# schematic_slave2_rotary.net
KiCad netlist of a schematic drawn in EAGLE
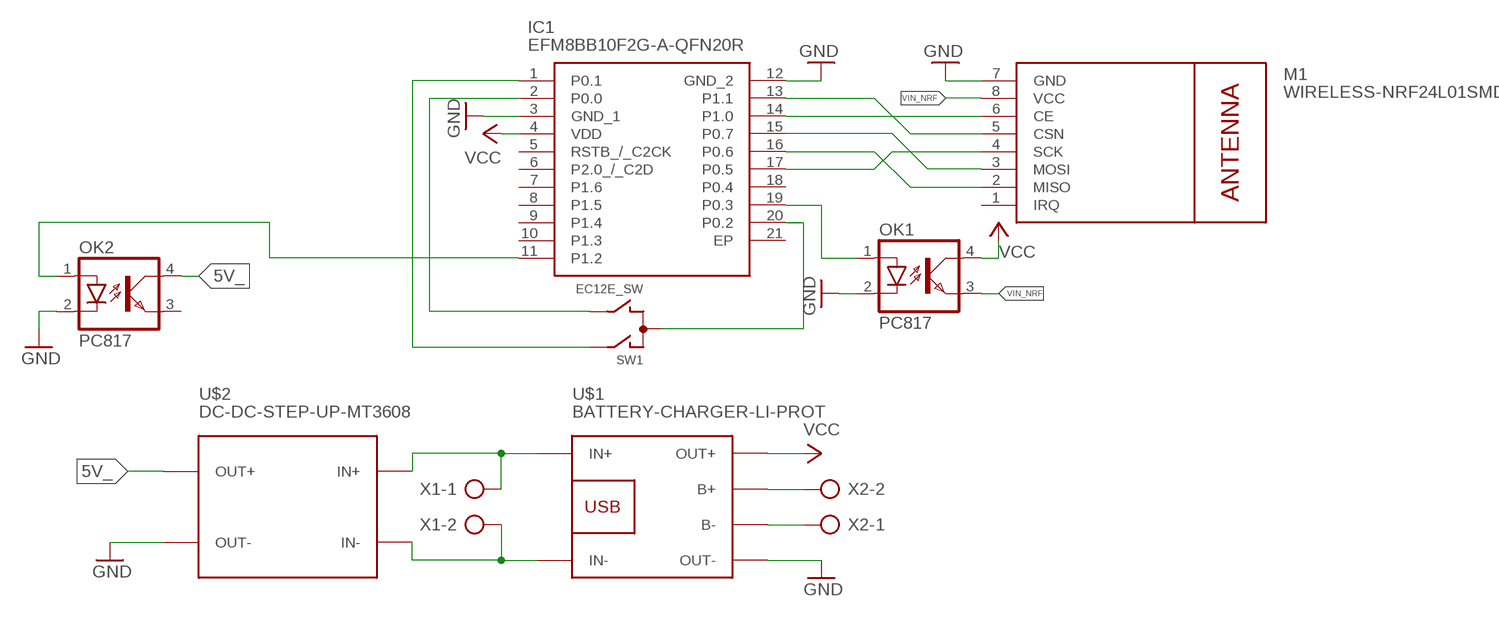
[diagram p0: schematic, sheet 1]

(export (version "E")
  (design (tool "Eeschema 10.0.6"))
  (components
    (comp (ref "IC1")
      (value "EFM8BB10F2G-A-QFN20R")
      (footprint "eagle-import:EFM8BB10F2GAQFN20R")
      (fields (field (name "MOUSER_PART_NUMBER") "634-8BB10F2GAQF20R"))
      (libsource (lib "eagle-import") (part "EFM8BB10F2G-A-QFN20R"))
    )
    (comp (ref "M1")
      (value "WIRELESS-NRF24L01SMD")
      (footprint "eagle-import:WIRELESS-NRF24L01-SMD")
      (libsource (lib "eagle-import") (part "WIRELESS-NRF24L01SMD"))
    )
    (comp (ref "OK1")
      (value "PC817")
      (footprint "eagle-import:DIL04")
      (fields (field (name "MPN") "PC817X4J000F"))
      (libsource (lib "eagle-import") (part "PC817"))
    )
    (comp (ref "OK2")
      (value "PC817")
      (footprint "eagle-import:DIL04")
      (fields (field (name "MPN") "PC817X4J000F"))
      (libsource (lib "eagle-import") (part "PC817"))
    )
    (comp (ref "SW1")
      (value "EC12E_SW")
      (footprint "eagle-import:ALPS_EC12E_SW")
      (fields (field (name "MPN") "EC12E2424407"))
      (libsource (lib "eagle-import") (part "EC12E_SW"))
    )
    (comp (ref "U$1")
      (value "BATTERY-CHARGER-LI-PROT")
      (footprint "eagle-import:BATTERY-CHARGER-LI-PROT")
      (libsource (lib "eagle-import") (part "BATTERY-CHARGER-LI-PROT"))
    )
    (comp (ref "U$2")
      (value "DC-DC-STEP-UP-MT3608")
      (footprint "eagle-import:DC-DC-STEP-UP-MT3608")
      (libsource (lib "eagle-import") (part "DC-DC-STEP-UP-MT3608"))
    )
    (comp (ref "X1")
      (value "AK500/2-H")
      (footprint "eagle-import:AK500_2-H")
      (libsource (lib "eagle-import") (part "AK500/2-H"))
    )
    (comp (ref "X2")
      (value "AK500/2-H")
      (footprint "eagle-import:AK500_2-H")
      (libsource (lib "eagle-import") (part "AK500/2-H"))
    )
  )
  (nets
    (net (code "1") (name "5V_") (class "Default")
      (node (ref "OK2") (pin "4") (pinfunction "COL_4") (pintype "passive"))
      (node (ref "U$2") (pin "OUT+") (pinfunction "OUT+_OUT+") (pintype "bidirectional"))
    )
    (net (code "2") (name "GND") (class "Default")
      (node (ref "IC1") (pin "12") (pinfunction "GND_2_12") (pintype "bidirectional"))
      (node (ref "IC1") (pin "3") (pinfunction "GND_1_3") (pintype "bidirectional"))
      (node (ref "M1") (pin "7") (pinfunction "GND_7") (pintype "power_in"))
      (node (ref "OK1") (pin "2") (pinfunction "C_2") (pintype "passive"))
      (node (ref "OK2") (pin "2") (pinfunction "C_2") (pintype "passive"))
      (node (ref "U$1") (pin "OUT-") (pinfunction "OUT-_OUT-") (pintype "bidirectional"))
      (node (ref "U$2") (pin "OUT-") (pinfunction "OUT-_OUT-") (pintype "bidirectional"))
    )
    (net (code "3") (name "Net-(IC1-P0.0)") (class "Default")
      (node (ref "IC1") (pin "2") (pinfunction "P0.0_2") (pintype "bidirectional"))
      (node (ref "SW1") (pin "B") (pinfunction "B_B") (pintype "passive"))
    )
    (net (code "4") (name "Net-(IC1-P0.1)") (class "Default")
      (node (ref "IC1") (pin "1") (pinfunction "P0.1_1") (pintype "bidirectional"))
      (node (ref "SW1") (pin "A") (pinfunction "A_A") (pintype "passive"))
    )
    (net (code "5") (name "Net-(IC1-P0.2)") (class "Default")
      (node (ref "IC1") (pin "20") (pinfunction "P0.2_20") (pintype "bidirectional"))
      (node (ref "SW1") (pin "C") (pinfunction "C_C") (pintype "passive"))
    )
    (net (code "6") (name "Net-(IC1-P0.3)") (class "Default")
      (node (ref "IC1") (pin "19") (pinfunction "P0.3_19") (pintype "bidirectional"))
      (node (ref "OK1") (pin "1") (pinfunction "A_1") (pintype "passive"))
    )
    (net (code "7") (name "Net-(IC1-P0.5)") (class "Default")
      (node (ref "IC1") (pin "17") (pinfunction "P0.5_17") (pintype "bidirectional"))
      (node (ref "M1") (pin "4") (pinfunction "SCK_4") (pintype "bidirectional"))
    )
    (net (code "8") (name "Net-(IC1-P0.6)") (class "Default")
      (node (ref "IC1") (pin "16") (pinfunction "P0.6_16") (pintype "bidirectional"))
      (node (ref "M1") (pin "2") (pinfunction "MISO_2") (pintype "bidirectional"))
    )
    (net (code "9") (name "Net-(IC1-P0.7)") (class "Default")
      (node (ref "IC1") (pin "15") (pinfunction "P0.7_15") (pintype "bidirectional"))
      (node (ref "M1") (pin "3") (pinfunction "MOSI_3") (pintype "bidirectional"))
    )
    (net (code "10") (name "Net-(IC1-P1.0)") (class "Default")
      (node (ref "IC1") (pin "14") (pinfunction "P1.0_14") (pintype "bidirectional"))
      (node (ref "M1") (pin "6") (pinfunction "CE_6") (pintype "bidirectional"))
    )
    (net (code "11") (name "Net-(IC1-P1.1)") (class "Default")
      (node (ref "IC1") (pin "13") (pinfunction "P1.1_13") (pintype "bidirectional"))
      (node (ref "M1") (pin "5") (pinfunction "CSN_5") (pintype "bidirectional"))
    )
    (net (code "12") (name "Net-(IC1-P1.2)") (class "Default")
      (node (ref "IC1") (pin "11") (pinfunction "P1.2_11") (pintype "bidirectional"))
      (node (ref "OK2") (pin "1") (pinfunction "A_1") (pintype "passive"))
    )
    (net (code "13") (name "Net-(X1A-KL)") (class "Default")
      (node (ref "U$1") (pin "IN+") (pinfunction "IN+_IN+") (pintype "bidirectional"))
      (node (ref "U$2") (pin "IN+") (pinfunction "IN+_IN+") (pintype "bidirectional"))
      (node (ref "X1") (pin "1") (pinfunction "KL_1") (pintype "passive"))
    )
    (net (code "14") (name "Net-(X1B-KL)") (class "Default")
      (node (ref "U$1") (pin "IN-") (pinfunction "IN-_IN-") (pintype "bidirectional"))
      (node (ref "U$2") (pin "IN-") (pinfunction "IN-_IN-") (pintype "bidirectional"))
      (node (ref "X1") (pin "2") (pinfunction "KL_2") (pintype "passive"))
    )
    (net (code "15") (name "Net-(X2A-KL)") (class "Default")
      (node (ref "U$1") (pin "B-") (pinfunction "B-_B-") (pintype "bidirectional"))
      (node (ref "X2") (pin "1") (pinfunction "KL_1") (pintype "passive"))
    )
    (net (code "16") (name "Net-(X2B-KL)") (class "Default")
      (node (ref "U$1") (pin "B+") (pinfunction "B+_B+") (pintype "bidirectional"))
      (node (ref "X2") (pin "2") (pinfunction "KL_2") (pintype "passive"))
    )
    (net (code "17") (name "VCC") (class "Default")
      (node (ref "IC1") (pin "4") (pinfunction "VDD_4") (pintype "bidirectional"))
      (node (ref "OK1") (pin "4") (pinfunction "COL_4") (pintype "passive"))
      (node (ref "U$1") (pin "OUT+") (pinfunction "OUT+_OUT+") (pintype "bidirectional"))
    )
    (net (code "18") (name "VIN_NRF") (class "Default")
      (node (ref "M1") (pin "8") (pinfunction "VCC_8") (pintype "power_in"))
      (node (ref "OK1") (pin "3") (pinfunction "EMIT_3") (pintype "passive"))
    )
    (net (code "19") (name "unconnected-(IC1-EP-Pad21)") (class "Default")
      (node (ref "IC1") (pin "21") (pinfunction "EP_21") (pintype "bidirectional"))
    )
    (net (code "20") (name "unconnected-(IC1-P0.4-Pad18)") (class "Default")
      (node (ref "IC1") (pin "18") (pinfunction "P0.4_18") (pintype "bidirectional"))
    )
    (net (code "21") (name "unconnected-(IC1-P1.3-Pad10)") (class "Default")
      (node (ref "IC1") (pin "10") (pinfunction "P1.3_10") (pintype "bidirectional"))
    )
    (net (code "22") (name "unconnected-(IC1-P1.4-Pad9)") (class "Default")
      (node (ref "IC1") (pin "9") (pinfunction "P1.4_9") (pintype "bidirectional"))
    )
    (net (code "23") (name "unconnected-(IC1-P1.5-Pad8)") (class "Default")
      (node (ref "IC1") (pin "8") (pinfunction "P1.5_8") (pintype "bidirectional"))
    )
    (net (code "24") (name "unconnected-(IC1-P1.6-Pad7)") (class "Default")
      (node (ref "IC1") (pin "7") (pinfunction "P1.6_7") (pintype "bidirectional"))
    )
    (net (code "25") (name "unconnected-(IC1-P2.0_{slash}_C2D-Pad6)") (class "Default")
      (node (ref "IC1") (pin "6") (pinfunction "P2.0_/_C2D_6") (pintype "bidirectional"))
    )
    (net (code "26") (name "unconnected-(IC1-RSTB_{slash}_C2CK-Pad5)") (class "Default")
      (node (ref "IC1") (pin "5") (pinfunction "RSTB_/_C2CK_5") (pintype "bidirectional"))
    )
    (net (code "27") (name "unconnected-(M1-IRQ-Pad1)") (class "Default")
      (node (ref "M1") (pin "1") (pinfunction "IRQ_1") (pintype "bidirectional"))
    )
    (net (code "28") (name "unconnected-(OK2-EMIT-Pad3)") (class "Default")
      (node (ref "OK2") (pin "3") (pinfunction "EMIT_3") (pintype "passive"))
    )
  )
)
